# Signals2uC.net
KiCad netlist of a schematic drawn in Altium Designer
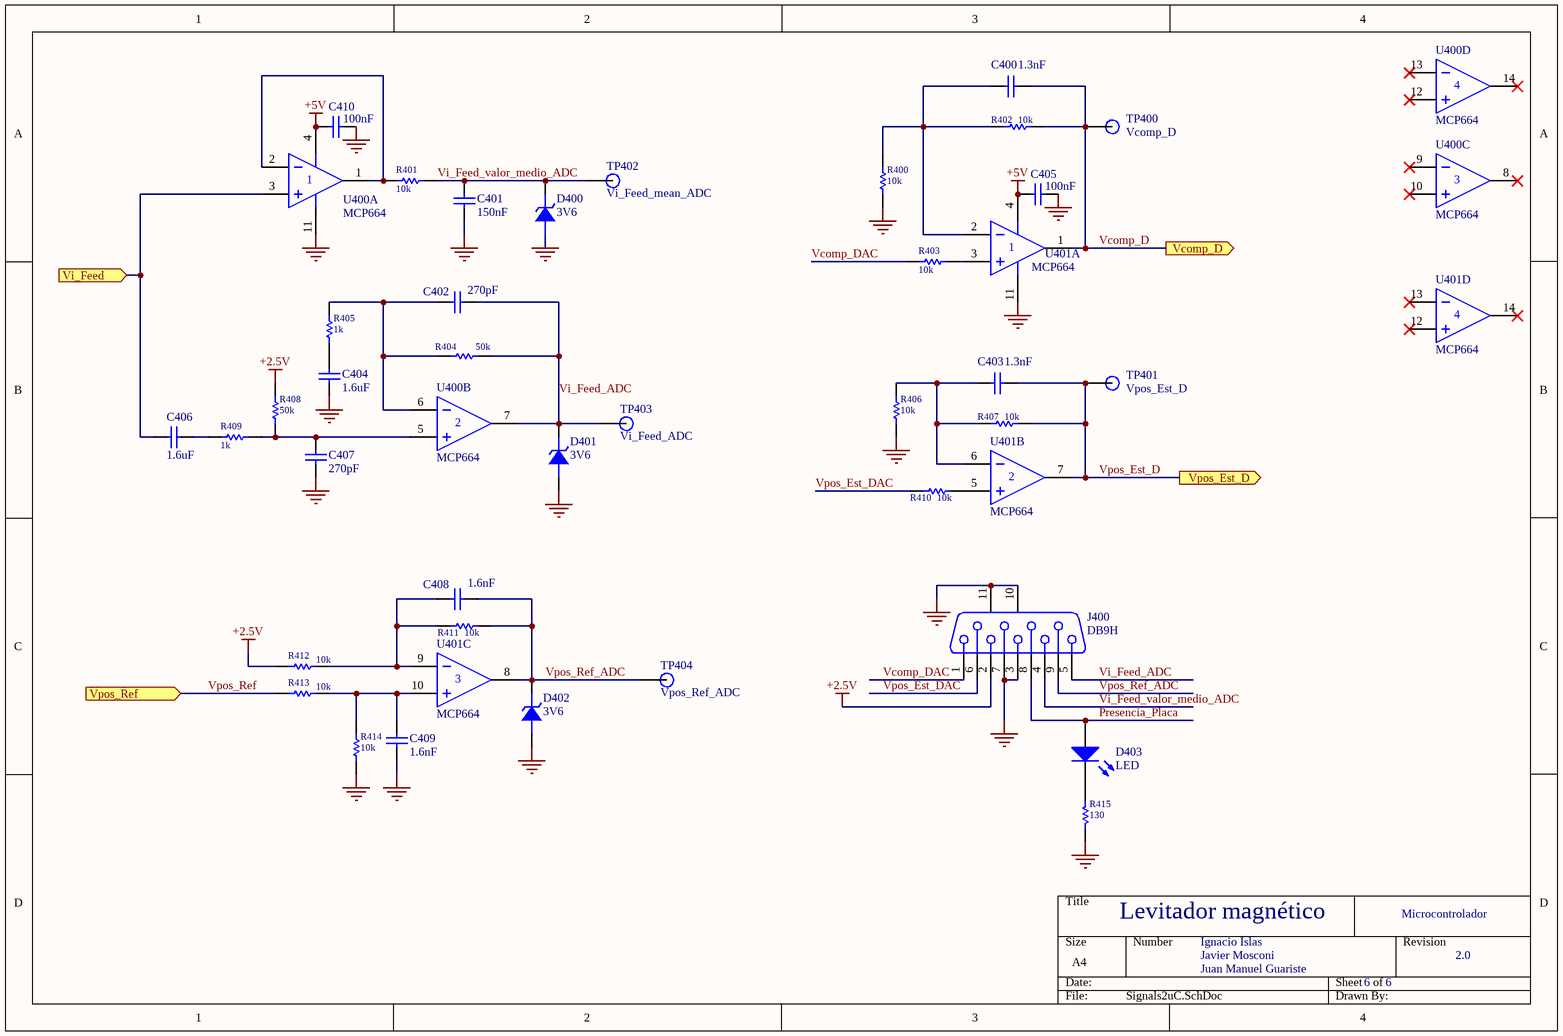
[diagram p0: Signals2uC.SchDoc]

(export (version "E")
  (design (tool "Eeschema 10.0.6"))
  (components
    (comp (ref "C400")
      (value "1.3nF")
      (footprint "C1206")
      (description "CAP CER 1300PF 50V NP0 1206")
      (fields (field (name "MANUFACTURER") "KEMET") (field (name "Comment") "Capacitor"))
      (libsource (lib "Levitador_GMI") (part "Capacitor"))
    )
    (comp (ref "C401")
      (value "150nF")
      (footprint "C1206")
      (description "CAP CER 0.15UF 50V X7R 1206")
      (fields (field (name "MANUFACTURER") "KYOCERA AVX") (field (name "Comment") "Capacitor"))
      (libsource (lib "Levitador_GMI") (part "Capacitor"))
    )
    (comp (ref "C402")
      (value "270pF")
      (footprint "C1206")
      (description "CAP CER 270PF 50V C0G/NP0 1206")
      (fields (field (name "MANUFACTURER") "KEMET") (field (name "Comment") "Capacitor"))
      (libsource (lib "Levitador_GMI") (part "Capacitor"))
    )
    (comp (ref "C403")
      (value "1.3nF")
      (footprint "C1206")
      (description "CAP CER 1300PF 50V NP0 1206")
      (fields (field (name "MANUFACTURER") "KEMET") (field (name "Comment") "Capacitor"))
      (libsource (lib "Levitador_GMI") (part "Capacitor"))
    )
    (comp (ref "C404")
      (value "1.6uF")
      (footprint "C1206")
      (description "CAP CER 1.5UF 10V X7R 1206")
      (fields (field (name "MANUFACTURER") "YAGEO") (field (name "Comment") "Capacitor"))
      (libsource (lib "Levitador_GMI") (part "Capacitor"))
    )
    (comp (ref "C405")
      (value "100nF")
      (footprint "C1206")
      (description "CAP CER 0.1UF 50V X7R 1206")
      (fields (field (name "MANUFACTURER") "Venkel") (field (name "Comment") "Capacitor"))
      (libsource (lib "Levitador_GMI") (part "Capacitor"))
    )
    (comp (ref "C406")
      (value "1.6uF")
      (footprint "C1206")
      (description "CAP CER 1.5UF 10V X7R 1206")
      (fields (field (name "MANUFACTURER") "YAGEO") (field (name "Comment") "Capacitor"))
      (libsource (lib "Levitador_GMI") (part "Capacitor"))
    )
    (comp (ref "C407")
      (value "270pF")
      (footprint "C1206")
      (description "CAP CER 270PF 50V C0G/NP0 1206")
      (fields (field (name "MANUFACTURER") "KEMET") (field (name "Comment") "Capacitor"))
      (libsource (lib "Levitador_GMI") (part "Capacitor"))
    )
    (comp (ref "C408")
      (value "1.6nF")
      (footprint "C1206")
      (description "CAP CER 1600PF 50V NP0 1206")
      (fields (field (name "MANUFACTURER") "KEMET") (field (name "Comment") "Capacitor"))
      (libsource (lib "Levitador_GMI") (part "Capacitor"))
    )
    (comp (ref "C409")
      (value "1.6nF")
      (footprint "C1206")
      (description "CAP CER 1600PF 50V NP0 1206")
      (fields (field (name "MANUFACTURER") "KEMET") (field (name "Comment") "Capacitor"))
      (libsource (lib "Levitador_GMI") (part "Capacitor"))
    )
    (comp (ref "C410")
      (value "100nF")
      (footprint "C1206")
      (description "CAP CER 0.1UF 50V X7R 1206")
      (fields (field (name "MANUFACTURER") "Venkel") (field (name "Comment") "Capacitor"))
      (libsource (lib "Levitador_GMI") (part "Capacitor"))
    )
    (comp (ref "D400")
      (value "3V6")
      (footprint "SMB")
      (description "DIODE ZENER 3.6V 3W SMB")
      (fields (field (name "MANUFACTURER") "onsemi") (field (name "Comment") "Diodo Zener"))
      (libsource (lib "Levitador_GMI") (part "Diodo Zener"))
    )
    (comp (ref "D401")
      (value "3V6")
      (footprint "SMB")
      (description "DIODE ZENER 3.6V 3W SMB")
      (fields (field (name "MANUFACTURER") "onsemi") (field (name "Comment") "Diodo Zener"))
      (libsource (lib "Levitador_GMI") (part "Diodo Zener"))
    )
    (comp (ref "D402")
      (value "3V6")
      (footprint "SMB")
      (description "DIODE ZENER 3.6V 3W SMB")
      (fields (field (name "MANUFACTURER") "onsemi") (field (name "Comment") "Diodo Zener"))
      (libsource (lib "Levitador_GMI") (part "Diodo Zener"))
    )
    (comp (ref "D403")
      (value "LED")
      (footprint "LED 1206 RED")
      (description "1206 RED SMD LED")
      (fields (field (name "MANUFACTURER") "American Opto Plus LED"))
      (libsource (lib "Levitador_GMI") (part "LED"))
    )
    (comp (ref "J400")
      (value "DB9H")
      (footprint "DB9H")
      (description "CONN D-SUB RCPT 9POS R/A SLDR")
      (fields (field (name "MANUFACTURER") "Assmann WSW Components"))
      (libsource (lib "Levitador_GMI") (part "DB9H"))
    )
    (comp (ref "R400")
      (value "10k")
      (footprint "Levitador_GMI:R1206")
      (description "RES 10K OHM 1% 1/4W 1206")
      (fields (field (name "MANUFACTURER") "YAGEO") (field (name "TOLERANCE") "1%"))
      (libsource (lib "Levitador_GMI") (part "R1206"))
    )
    (comp (ref "R401")
      (value "10k")
      (footprint "Levitador_GMI:R1206")
      (description "RES 10K OHM 1% 1/4W 1206")
      (fields (field (name "MANUFACTURER") "YAGEO") (field (name "TOLERANCE") "1%"))
      (libsource (lib "Levitador_GMI") (part "R1206"))
    )
    (comp (ref "R402")
      (value "10k")
      (footprint "Levitador_GMI:R1206")
      (description "RES 10K OHM 1% 1/4W 1206")
      (fields (field (name "MANUFACTURER") "YAGEO") (field (name "TOLERANCE") "1%"))
      (libsource (lib "Levitador_GMI") (part "R1206"))
    )
    (comp (ref "R403")
      (value "10k")
      (footprint "Levitador_GMI:R1206")
      (description "RES 10K OHM 1% 1/4W 1206")
      (fields (field (name "MANUFACTURER") "YAGEO") (field (name "TOLERANCE") "1%"))
      (libsource (lib "Levitador_GMI") (part "R1206"))
    )
    (comp (ref "R404")
      (value "50k")
      (footprint "Levitador_GMI:R1206")
      (description "RES SMD 50K OHM 0.1% 1/4W 1206")
      (fields (field (name "MANUFACTURER") "YAGEO") (field (name "TOLERANCE") "0.1%"))
      (libsource (lib "Levitador_GMI") (part "R1206"))
    )
    (comp (ref "R405")
      (value "1k")
      (footprint "Levitador_GMI:R1206")
      (description "RES 1K OHM 1% 1/4W 1206")
      (fields (field (name "MANUFACTURER") "Stackpole Electronics Inc") (field (name "TOLERANCE") "1%"))
      (libsource (lib "Levitador_GMI") (part "R1206"))
    )
    (comp (ref "R406")
      (value "10k")
      (footprint "Levitador_GMI:R1206")
      (description "RES 10K OHM 1% 1/4W 1206")
      (fields (field (name "MANUFACTURER") "YAGEO") (field (name "TOLERANCE") "1%"))
      (libsource (lib "Levitador_GMI") (part "R1206"))
    )
    (comp (ref "R407")
      (value "10k")
      (footprint "Levitador_GMI:R1206")
      (description "RES 10K OHM 1% 1/4W 1206")
      (fields (field (name "MANUFACTURER") "YAGEO") (field (name "TOLERANCE") "1%"))
      (libsource (lib "Levitador_GMI") (part "R1206"))
    )
    (comp (ref "R408")
      (value "50k")
      (footprint "Levitador_GMI:R1206")
      (description "RES SMD 50K OHM 0.1% 1/4W 1206")
      (fields (field (name "MANUFACTURER") "YAGEO") (field (name "TOLERANCE") "0.1%"))
      (libsource (lib "Levitador_GMI") (part "R1206"))
    )
    (comp (ref "R409")
      (value "1k")
      (footprint "Levitador_GMI:R1206")
      (description "RES 1K OHM 1% 1/4W 1206")
      (fields (field (name "MANUFACTURER") "Stackpole Electronics Inc") (field (name "TOLERANCE") "1%"))
      (libsource (lib "Levitador_GMI") (part "R1206"))
    )
    (comp (ref "R410")
      (value "10k")
      (footprint "Levitador_GMI:R1206")
      (description "RES 10K OHM 1% 1/4W 1206")
      (fields (field (name "MANUFACTURER") "YAGEO") (field (name "TOLERANCE") "1%"))
      (libsource (lib "Levitador_GMI") (part "R1206"))
    )
    (comp (ref "R411")
      (value "10k")
      (footprint "Levitador_GMI:R1206")
      (description "RES 10K OHM 1% 1/4W 1206")
      (fields (field (name "MANUFACTURER") "YAGEO") (field (name "TOLERANCE") "1%"))
      (libsource (lib "Levitador_GMI") (part "R1206"))
    )
    (comp (ref "R412")
      (value "10k")
      (footprint "Levitador_GMI:R1206")
      (description "RES 10K OHM 1% 1/4W 1206")
      (fields (field (name "MANUFACTURER") "YAGEO") (field (name "TOLERANCE") "1%"))
      (libsource (lib "Levitador_GMI") (part "R1206"))
    )
    (comp (ref "R413")
      (value "10k")
      (footprint "Levitador_GMI:R1206")
      (description "RES 10K OHM 1% 1/4W 1206")
      (fields (field (name "MANUFACTURER") "YAGEO") (field (name "TOLERANCE") "1%"))
      (libsource (lib "Levitador_GMI") (part "R1206"))
    )
    (comp (ref "R414")
      (value "10k")
      (footprint "Levitador_GMI:R1206")
      (description "RES 10K OHM 1% 1/4W 1206")
      (fields (field (name "MANUFACTURER") "YAGEO") (field (name "TOLERANCE") "1%"))
      (libsource (lib "Levitador_GMI") (part "R1206"))
    )
    (comp (ref "R415")
      (value "130")
      (footprint "Levitador_GMI:R1206")
      (description "RES 130 OHM 1% 1/4W 1206")
      (fields (field (name "MANUFACTURER") "Stackpole Electronics Inc") (field (name "TOLERANCE") "1%"))
      (libsource (lib "Levitador_GMI") (part "R1206"))
    )
    (comp (ref "TP400")
      (value "Vcomp_D")
      (footprint "TestPoint Keystone 5000 Silver-Red")
      (description "PC TEST POINT MINIATURE RED")
      (fields (field (name "MANUFACTURER") "Keystone Electronics"))
      (libsource (lib "Levitador_GMI") (part "Testpoint"))
    )
    (comp (ref "TP401")
      (value "Vpos_Est_D")
      (footprint "TestPoint Keystone 5000 Silver-Red")
      (description "PC TEST POINT MINIATURE RED")
      (fields (field (name "MANUFACTURER") "Keystone Electronics"))
      (libsource (lib "Levitador_GMI") (part "Testpoint"))
    )
    (comp (ref "TP402")
      (value "Vi_Feed_mean_ADC")
      (footprint "TestPoint Keystone 5000 Silver-Red")
      (description "PC TEST POINT MINIATURE RED")
      (fields (field (name "MANUFACTURER") "Keystone Electronics"))
      (libsource (lib "Levitador_GMI") (part "Testpoint"))
    )
    (comp (ref "TP403")
      (value "Vi_Feed_ADC")
      (footprint "TestPoint Keystone 5000 Silver-Red")
      (description "PC TEST POINT MINIATURE RED")
      (fields (field (name "MANUFACTURER") "Keystone Electronics"))
      (libsource (lib "Levitador_GMI") (part "Testpoint"))
    )
    (comp (ref "TP404")
      (value "Vpos_Ref_ADC")
      (footprint "TestPoint Keystone 5000 Silver-Red")
      (description "PC TEST POINT MINIATURE RED")
      (fields (field (name "MANUFACTURER") "Keystone Electronics"))
      (libsource (lib "Levitador_GMI") (part "Testpoint"))
    )
    (comp (ref "U400")
      (value "MCP664")
      (footprint "SOIC14")
      (description "IC OPAMP GP 4 CIRCUIT 14TSSOP")
      (fields (field (name "MANUFACTURER") "Microchip Technology"))
      (libsource (lib "Levitador_GMI") (part "MCP664"))
    )
    (comp (ref "U401")
      (value "MCP664")
      (footprint "SOIC14")
      (description "IC OPAMP GP 4 CIRCUIT 14TSSOP")
      (fields (field (name "MANUFACTURER") "Microchip Technology"))
      (libsource (lib "Levitador_GMI") (part "MCP664"))
    )
  )
  (nets
    (net (code "1") (name "+2.5V") (class "Default")
      (node (ref "J400") (pin "2") (pinfunction "2_2") (pintype "passive"))
      (node (ref "R408") (pin "2") (pinfunction "2_2") (pintype "passive"))
      (node (ref "R412") (pin "1") (pinfunction "1_1") (pintype "passive"))
    )
    (net (code "2") (name "+5V") (class "Default")
      (node (ref "C405") (pin "1") (pinfunction "1_1") (pintype "passive"))
      (node (ref "C410") (pin "1") (pinfunction "1_1") (pintype "passive"))
      (node (ref "U400") (pin "4") (pinfunction "V+_4") (pintype "power_in"))
      (node (ref "U401") (pin "4") (pinfunction "V+_4") (pintype "power_in"))
    )
    (net (code "3") (name "/Presencia_Placa") (class "Default")
      (node (ref "D403") (pin "1") (pinfunction "A_1") (pintype "passive"))
      (node (ref "J400") (pin "8") (pinfunction "8_8") (pintype "passive"))
    )
    (net (code "4") (name "/Vcomp_D") (class "Default")
      (node (ref "C400") (pin "1") (pinfunction "1_1") (pintype "passive"))
      (node (ref "R402") (pin "2") (pinfunction "2_2") (pintype "passive"))
      (node (ref "TP400") (pin "1") (pinfunction "1_1") (pintype "passive"))
      (node (ref "U401") (pin "1") (pinfunction "OUT_1") (pintype "passive"))
    )
    (net (code "5") (name "/Vcomp_DAC") (class "Default")
      (node (ref "J400") (pin "1") (pinfunction "1_1") (pintype "passive"))
      (node (ref "R403") (pin "1") (pinfunction "1_1") (pintype "passive"))
    )
    (net (code "6") (name "/Vi_Feed") (class "Default")
      (node (ref "C406") (pin "1") (pinfunction "1_1") (pintype "passive"))
      (node (ref "U400") (pin "3") (pinfunction "IN+_3") (pintype "passive"))
    )
    (net (code "7") (name "/Vi_Feed_ADC") (class "Default")
      (node (ref "C402") (pin "1") (pinfunction "1_1") (pintype "passive"))
      (node (ref "D401") (pin "2") (pinfunction "2_2") (pintype "passive"))
      (node (ref "J400") (pin "5") (pinfunction "5_5") (pintype "passive"))
      (node (ref "R404") (pin "2") (pinfunction "2_2") (pintype "passive"))
      (node (ref "TP403") (pin "1") (pinfunction "1_1") (pintype "passive"))
      (node (ref "U400") (pin "7") (pinfunction "OUT_7") (pintype "passive"))
    )
    (net (code "8") (name "/Vi_Feed_valor_medio_ADC") (class "Default")
      (node (ref "C401") (pin "2") (pinfunction "2_2") (pintype "passive"))
      (node (ref "D400") (pin "2") (pinfunction "2_2") (pintype "passive"))
      (node (ref "J400") (pin "4") (pinfunction "4_4") (pintype "passive"))
      (node (ref "R401") (pin "2") (pinfunction "2_2") (pintype "passive"))
      (node (ref "TP402") (pin "1") (pinfunction "1_1") (pintype "passive"))
    )
    (net (code "9") (name "/Vpos_Est_D") (class "Default")
      (node (ref "C403") (pin "1") (pinfunction "1_1") (pintype "passive"))
      (node (ref "R407") (pin "2") (pinfunction "2_2") (pintype "passive"))
      (node (ref "TP401") (pin "1") (pinfunction "1_1") (pintype "passive"))
      (node (ref "U401") (pin "7") (pinfunction "OUT_7") (pintype "passive"))
    )
    (net (code "10") (name "/Vpos_Est_DAC") (class "Default")
      (node (ref "J400") (pin "6") (pinfunction "6_6") (pintype "passive"))
      (node (ref "R410") (pin "1") (pinfunction "1_1") (pintype "passive"))
    )
    (net (code "11") (name "/Vpos_Ref") (class "Default")
      (node (ref "R413") (pin "1") (pinfunction "1_1") (pintype "passive"))
    )
    (net (code "12") (name "/Vpos_Ref_ADC") (class "Default")
      (node (ref "C408") (pin "1") (pinfunction "1_1") (pintype "passive"))
      (node (ref "D402") (pin "2") (pinfunction "2_2") (pintype "passive"))
      (node (ref "J400") (pin "9") (pinfunction "9_9") (pintype "passive"))
      (node (ref "R411") (pin "2") (pinfunction "2_2") (pintype "passive"))
      (node (ref "TP404") (pin "1") (pinfunction "1_1") (pintype "passive"))
      (node (ref "U401") (pin "8") (pinfunction "OUT_8") (pintype "passive"))
    )
    (net (code "13") (name "GND") (class "Default")
      (node (ref "C401") (pin "1") (pinfunction "1_1") (pintype "passive"))
      (node (ref "C404") (pin "2") (pinfunction "2_2") (pintype "passive"))
      (node (ref "C405") (pin "2") (pinfunction "2_2") (pintype "passive"))
      (node (ref "C407") (pin "1") (pinfunction "1_1") (pintype "passive"))
      (node (ref "C409") (pin "2") (pinfunction "2_2") (pintype "passive"))
      (node (ref "C410") (pin "2") (pinfunction "2_2") (pintype "passive"))
      (node (ref "D400") (pin "1") (pinfunction "1_1") (pintype "passive"))
      (node (ref "D401") (pin "1") (pinfunction "1_1") (pintype "passive"))
      (node (ref "D402") (pin "1") (pinfunction "1_1") (pintype "passive"))
      (node (ref "J400") (pin "10") (pinfunction "MH1_10") (pintype "passive"))
      (node (ref "J400") (pin "11") (pinfunction "MH2_11") (pintype "passive"))
      (node (ref "J400") (pin "3") (pinfunction "3_3") (pintype "passive"))
      (node (ref "J400") (pin "7") (pinfunction "7_7") (pintype "passive"))
      (node (ref "R400") (pin "1") (pinfunction "1_1") (pintype "passive"))
      (node (ref "R406") (pin "1") (pinfunction "1_1") (pintype "passive"))
      (node (ref "R414") (pin "1") (pinfunction "1_1") (pintype "passive"))
      (node (ref "R415") (pin "1") (pinfunction "1_1") (pintype "passive"))
      (node (ref "U400") (pin "11") (pinfunction "V-_11") (pintype "power_in"))
      (node (ref "U401") (pin "11") (pinfunction "V-_11") (pintype "power_in"))
    )
    (net (code "14") (name "Net-(C404-Pad1)") (class "Default")
      (node (ref "C404") (pin "1") (pinfunction "1_1") (pintype "passive"))
      (node (ref "R405") (pin "1") (pinfunction "1_1") (pintype "passive"))
    )
    (net (code "15") (name "Net-(C406-Pad2)") (class "Default")
      (node (ref "C406") (pin "2") (pinfunction "2_2") (pintype "passive"))
      (node (ref "R409") (pin "1") (pinfunction "1_1") (pintype "passive"))
    )
    (net (code "16") (name "Net-(D403-K)") (class "Default")
      (node (ref "D403") (pin "2") (pinfunction "K_2") (pintype "passive"))
      (node (ref "R415") (pin "2") (pinfunction "2_2") (pintype "passive"))
    )
    (net (code "17") (name "Net-(U400A-IN-)") (class "Default")
      (node (ref "R401") (pin "1") (pinfunction "1_1") (pintype "passive"))
      (node (ref "U400") (pin "1") (pinfunction "OUT_1") (pintype "passive"))
      (node (ref "U400") (pin "2") (pinfunction "IN-_2") (pintype "passive"))
    )
    (net (code "18") (name "Net-(U400B-IN+)") (class "Default")
      (node (ref "C407") (pin "2") (pinfunction "2_2") (pintype "passive"))
      (node (ref "R408") (pin "1") (pinfunction "1_1") (pintype "passive"))
      (node (ref "R409") (pin "2") (pinfunction "2_2") (pintype "passive"))
      (node (ref "U400") (pin "5") (pinfunction "IN+_5") (pintype "passive"))
    )
    (net (code "19") (name "Net-(U400B-IN-)") (class "Default")
      (node (ref "C402") (pin "2") (pinfunction "2_2") (pintype "passive"))
      (node (ref "R404") (pin "1") (pinfunction "1_1") (pintype "passive"))
      (node (ref "R405") (pin "2") (pinfunction "2_2") (pintype "passive"))
      (node (ref "U400") (pin "6") (pinfunction "IN-_6") (pintype "passive"))
    )
    (net (code "20") (name "Net-(U401A-IN+)") (class "Default")
      (node (ref "R403") (pin "2") (pinfunction "2_2") (pintype "passive"))
      (node (ref "U401") (pin "3") (pinfunction "IN+_3") (pintype "passive"))
    )
    (net (code "21") (name "Net-(U401A-IN-)") (class "Default")
      (node (ref "C400") (pin "2") (pinfunction "2_2") (pintype "passive"))
      (node (ref "R400") (pin "2") (pinfunction "2_2") (pintype "passive"))
      (node (ref "R402") (pin "1") (pinfunction "1_1") (pintype "passive"))
      (node (ref "U401") (pin "2") (pinfunction "IN-_2") (pintype "passive"))
    )
    (net (code "22") (name "Net-(U401B-IN+)") (class "Default")
      (node (ref "R410") (pin "2") (pinfunction "2_2") (pintype "passive"))
      (node (ref "U401") (pin "5") (pinfunction "IN+_5") (pintype "passive"))
    )
    (net (code "23") (name "Net-(U401B-IN-)") (class "Default")
      (node (ref "C403") (pin "2") (pinfunction "2_2") (pintype "passive"))
      (node (ref "R406") (pin "2") (pinfunction "2_2") (pintype "passive"))
      (node (ref "R407") (pin "1") (pinfunction "1_1") (pintype "passive"))
      (node (ref "U401") (pin "6") (pinfunction "IN-_6") (pintype "passive"))
    )
    (net (code "24") (name "Net-(U401C-IN+)") (class "Default")
      (node (ref "C409") (pin "1") (pinfunction "1_1") (pintype "passive"))
      (node (ref "R413") (pin "2") (pinfunction "2_2") (pintype "passive"))
      (node (ref "R414") (pin "2") (pinfunction "2_2") (pintype "passive"))
      (node (ref "U401") (pin "10") (pinfunction "IN+_10") (pintype "passive"))
    )
    (net (code "25") (name "Net-(U401C-IN-)") (class "Default")
      (node (ref "C408") (pin "2") (pinfunction "2_2") (pintype "passive"))
      (node (ref "R411") (pin "1") (pinfunction "1_1") (pintype "passive"))
      (node (ref "R412") (pin "2") (pinfunction "2_2") (pintype "passive"))
      (node (ref "U401") (pin "9") (pinfunction "IN-_9") (pintype "passive"))
    )
    (net (code "26") (name "unconnected-(U400C-IN+-Pad10)") (class "Default")
      (node (ref "U400") (pin "10") (pinfunction "IN+_10") (pintype "passive+no_connect"))
    )
    (net (code "27") (name "unconnected-(U400C-IN--Pad9)") (class "Default")
      (node (ref "U400") (pin "9") (pinfunction "IN-_9") (pintype "passive+no_connect"))
    )
    (net (code "28") (name "unconnected-(U400C-OUT-Pad8)") (class "Default")
      (node (ref "U400") (pin "8") (pinfunction "OUT_8") (pintype "passive+no_connect"))
    )
    (net (code "29") (name "unconnected-(U400D-IN+-Pad12)") (class "Default")
      (node (ref "U400") (pin "12") (pinfunction "IN+_12") (pintype "passive+no_connect"))
    )
    (net (code "30") (name "unconnected-(U400D-IN--Pad13)") (class "Default")
      (node (ref "U400") (pin "13") (pinfunction "IN-_13") (pintype "passive+no_connect"))
    )
    (net (code "31") (name "unconnected-(U400D-OUT-Pad14)") (class "Default")
      (node (ref "U400") (pin "14") (pinfunction "OUT_14") (pintype "passive+no_connect"))
    )
    (net (code "32") (name "unconnected-(U401D-IN+-Pad12)") (class "Default")
      (node (ref "U401") (pin "12") (pinfunction "IN+_12") (pintype "passive+no_connect"))
    )
    (net (code "33") (name "unconnected-(U401D-IN--Pad13)") (class "Default")
      (node (ref "U401") (pin "13") (pinfunction "IN-_13") (pintype "passive+no_connect"))
    )
    (net (code "34") (name "unconnected-(U401D-OUT-Pad14)") (class "Default")
      (node (ref "U401") (pin "14") (pinfunction "OUT_14") (pintype "passive+no_connect"))
    )
  )
)
